# stereo_mixer_quasi_diff_vertical.net
KiCad netlist of a schematic drawn in EAGLE
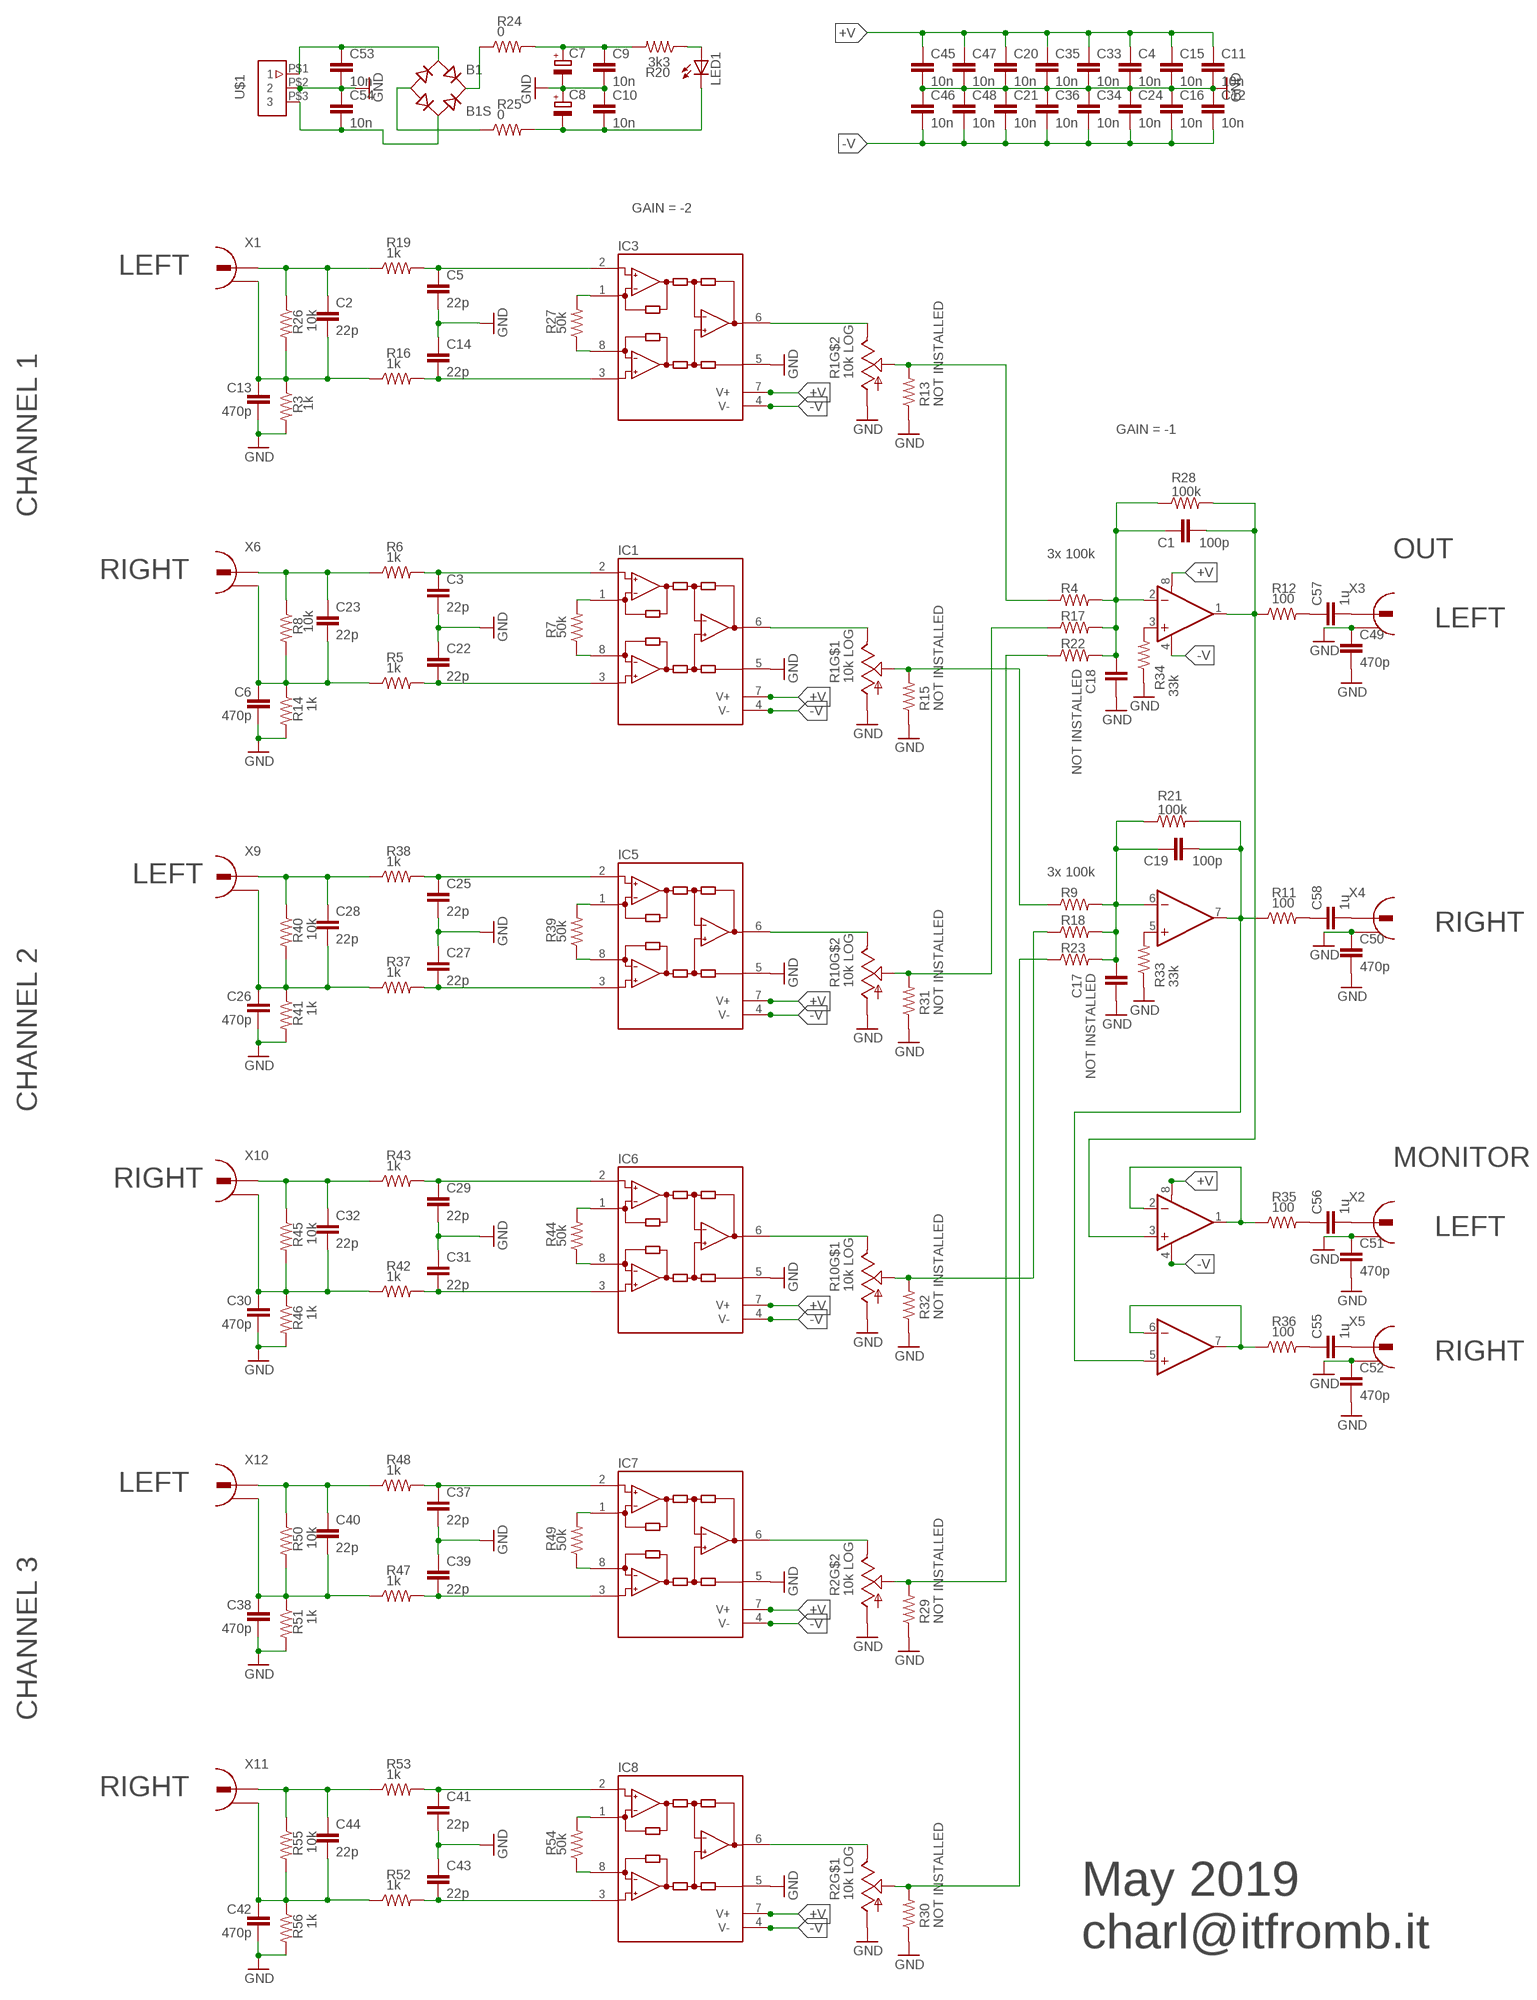
[diagram p0: schematic, sheet 1]

(export (version "E")
  (design (tool "Eeschema 10.0.6"))
  (components
    (comp (ref "B1")
      (value "B1S")
      (footprint "eagle-import:MBS")
      (libsource (lib "eagle-import") (part "BS1"))
    )
    (comp (ref "C1")
      (value "100p")
      (footprint "eagle-import:C1206")
      (libsource (lib "eagle-import") (part "C-EUC1206"))
    )
    (comp (ref "C2")
      (value "22p")
      (footprint "eagle-import:C1206")
      (libsource (lib "eagle-import") (part "C-EUC1206"))
    )
    (comp (ref "C3")
      (value "22p")
      (footprint "eagle-import:C1206")
      (libsource (lib "eagle-import") (part "C-EUC1206"))
    )
    (comp (ref "C4")
      (value "10n")
      (footprint "eagle-import:C1206")
      (libsource (lib "eagle-import") (part "C-EUC1206"))
    )
    (comp (ref "C5")
      (value "22p")
      (footprint "eagle-import:C1206")
      (libsource (lib "eagle-import") (part "C-EUC1206"))
    )
    (comp (ref "C6")
      (value "470p")
      (footprint "eagle-import:C1206")
      (libsource (lib "eagle-import") (part "C-EUC1206"))
    )
    (comp (ref "C7")
      (value "CPOL-EUSANYO_SMD_F12")
      (footprint "eagle-import:SANYO-OSCON_SMD_F12")
      (libsource (lib "eagle-import") (part "CPOL-EUSANYO_SMD_F12"))
    )
    (comp (ref "C8")
      (value "CPOL-EUSANYO_SMD_F12")
      (footprint "eagle-import:SANYO-OSCON_SMD_F12")
      (libsource (lib "eagle-import") (part "CPOL-EUSANYO_SMD_F12"))
    )
    (comp (ref "C9")
      (value "10n")
      (footprint "eagle-import:C1206")
      (libsource (lib "eagle-import") (part "C-EUC1206"))
    )
    (comp (ref "C10")
      (value "10n")
      (footprint "eagle-import:C1206")
      (libsource (lib "eagle-import") (part "C-EUC1206"))
    )
    (comp (ref "C11")
      (value "10n")
      (footprint "eagle-import:C1206")
      (libsource (lib "eagle-import") (part "C-EUC1206"))
    )
    (comp (ref "C12")
      (value "10n")
      (footprint "eagle-import:C1206")
      (libsource (lib "eagle-import") (part "C-EUC1206"))
    )
    (comp (ref "C13")
      (value "470p")
      (footprint "eagle-import:C1206")
      (libsource (lib "eagle-import") (part "C-EUC1206"))
    )
    (comp (ref "C14")
      (value "22p")
      (footprint "eagle-import:C1206")
      (libsource (lib "eagle-import") (part "C-EUC1206"))
    )
    (comp (ref "C15")
      (value "10n")
      (footprint "eagle-import:C1206")
      (libsource (lib "eagle-import") (part "C-EUC1206"))
    )
    (comp (ref "C16")
      (value "10n")
      (footprint "eagle-import:C1206")
      (libsource (lib "eagle-import") (part "C-EUC1206"))
    )
    (comp (ref "C17")
      (value "NOT INSTALLED")
      (footprint "eagle-import:C1206")
      (libsource (lib "eagle-import") (part "C-EUC1206"))
    )
    (comp (ref "C18")
      (value "NOT INSTALLED")
      (footprint "eagle-import:C1206")
      (libsource (lib "eagle-import") (part "C-EUC1206"))
    )
    (comp (ref "C19")
      (value "100p")
      (footprint "eagle-import:C1206")
      (libsource (lib "eagle-import") (part "C-EUC1206"))
    )
    (comp (ref "C20")
      (value "10n")
      (footprint "eagle-import:C1206")
      (libsource (lib "eagle-import") (part "C-EUC1206"))
    )
    (comp (ref "C21")
      (value "10n")
      (footprint "eagle-import:C1206")
      (libsource (lib "eagle-import") (part "C-EUC1206"))
    )
    (comp (ref "C22")
      (value "22p")
      (footprint "eagle-import:C1206")
      (libsource (lib "eagle-import") (part "C-EUC1206"))
    )
    (comp (ref "C23")
      (value "22p")
      (footprint "eagle-import:C1206")
      (libsource (lib "eagle-import") (part "C-EUC1206"))
    )
    (comp (ref "C24")
      (value "10n")
      (footprint "eagle-import:C1206")
      (libsource (lib "eagle-import") (part "C-EUC1206"))
    )
    (comp (ref "C25")
      (value "22p")
      (footprint "eagle-import:C1206")
      (libsource (lib "eagle-import") (part "C-EUC1206"))
    )
    (comp (ref "C26")
      (value "470p")
      (footprint "eagle-import:C1206")
      (libsource (lib "eagle-import") (part "C-EUC1206"))
    )
    (comp (ref "C27")
      (value "22p")
      (footprint "eagle-import:C1206")
      (libsource (lib "eagle-import") (part "C-EUC1206"))
    )
    (comp (ref "C28")
      (value "22p")
      (footprint "eagle-import:C1206")
      (libsource (lib "eagle-import") (part "C-EUC1206"))
    )
    (comp (ref "C29")
      (value "22p")
      (footprint "eagle-import:C1206")
      (libsource (lib "eagle-import") (part "C-EUC1206"))
    )
    (comp (ref "C30")
      (value "470p")
      (footprint "eagle-import:C1206")
      (libsource (lib "eagle-import") (part "C-EUC1206"))
    )
    (comp (ref "C31")
      (value "22p")
      (footprint "eagle-import:C1206")
      (libsource (lib "eagle-import") (part "C-EUC1206"))
    )
    (comp (ref "C32")
      (value "22p")
      (footprint "eagle-import:C1206")
      (libsource (lib "eagle-import") (part "C-EUC1206"))
    )
    (comp (ref "C33")
      (value "10n")
      (footprint "eagle-import:C1206")
      (libsource (lib "eagle-import") (part "C-EUC1206"))
    )
    (comp (ref "C34")
      (value "10n")
      (footprint "eagle-import:C1206")
      (libsource (lib "eagle-import") (part "C-EUC1206"))
    )
    (comp (ref "C35")
      (value "10n")
      (footprint "eagle-import:C1206")
      (libsource (lib "eagle-import") (part "C-EUC1206"))
    )
    (comp (ref "C36")
      (value "10n")
      (footprint "eagle-import:C1206")
      (libsource (lib "eagle-import") (part "C-EUC1206"))
    )
    (comp (ref "C37")
      (value "22p")
      (footprint "eagle-import:C1206")
      (libsource (lib "eagle-import") (part "C-EUC1206"))
    )
    (comp (ref "C38")
      (value "470p")
      (footprint "eagle-import:C1206")
      (libsource (lib "eagle-import") (part "C-EUC1206"))
    )
    (comp (ref "C39")
      (value "22p")
      (footprint "eagle-import:C1206")
      (libsource (lib "eagle-import") (part "C-EUC1206"))
    )
    (comp (ref "C40")
      (value "22p")
      (footprint "eagle-import:C1206")
      (libsource (lib "eagle-import") (part "C-EUC1206"))
    )
    (comp (ref "C41")
      (value "22p")
      (footprint "eagle-import:C1206")
      (libsource (lib "eagle-import") (part "C-EUC1206"))
    )
    (comp (ref "C42")
      (value "470p")
      (footprint "eagle-import:C1206")
      (libsource (lib "eagle-import") (part "C-EUC1206"))
    )
    (comp (ref "C43")
      (value "22p")
      (footprint "eagle-import:C1206")
      (libsource (lib "eagle-import") (part "C-EUC1206"))
    )
    (comp (ref "C44")
      (value "22p")
      (footprint "eagle-import:C1206")
      (libsource (lib "eagle-import") (part "C-EUC1206"))
    )
    (comp (ref "C45")
      (value "10n")
      (footprint "eagle-import:C1206")
      (libsource (lib "eagle-import") (part "C-EUC1206"))
    )
    (comp (ref "C46")
      (value "10n")
      (footprint "eagle-import:C1206")
      (libsource (lib "eagle-import") (part "C-EUC1206"))
    )
    (comp (ref "C47")
      (value "10n")
      (footprint "eagle-import:C1206")
      (libsource (lib "eagle-import") (part "C-EUC1206"))
    )
    (comp (ref "C48")
      (value "10n")
      (footprint "eagle-import:C1206")
      (libsource (lib "eagle-import") (part "C-EUC1206"))
    )
    (comp (ref "C49")
      (value "470p")
      (footprint "eagle-import:C1206")
      (libsource (lib "eagle-import") (part "C-EUC1206"))
    )
    (comp (ref "C50")
      (value "470p")
      (footprint "eagle-import:C1206")
      (libsource (lib "eagle-import") (part "C-EUC1206"))
    )
    (comp (ref "C51")
      (value "470p")
      (footprint "eagle-import:C1206")
      (libsource (lib "eagle-import") (part "C-EUC1206"))
    )
    (comp (ref "C52")
      (value "470p")
      (footprint "eagle-import:C1206")
      (libsource (lib "eagle-import") (part "C-EUC1206"))
    )
    (comp (ref "C53")
      (value "10n")
      (footprint "eagle-import:C1206")
      (libsource (lib "eagle-import") (part "C-EUC1206"))
    )
    (comp (ref "C54")
      (value "10n")
      (footprint "eagle-import:C1206")
      (libsource (lib "eagle-import") (part "C-EUC1206"))
    )
    (comp (ref "C55")
      (value "1u")
      (footprint "eagle-import:C1206")
      (libsource (lib "eagle-import") (part "C-EUC1206"))
    )
    (comp (ref "C56")
      (value "1u")
      (footprint "eagle-import:C1206")
      (libsource (lib "eagle-import") (part "C-EUC1206"))
    )
    (comp (ref "C57")
      (value "1u")
      (footprint "eagle-import:C1206")
      (libsource (lib "eagle-import") (part "C-EUC1206"))
    )
    (comp (ref "C58")
      (value "1u")
      (footprint "eagle-import:C1206")
      (libsource (lib "eagle-import") (part "C-EUC1206"))
    )
    (comp (ref "IC1")
      (value "INA118U")
      (footprint "eagle-import:SO08")
      (fields (field (name "MF") "TEXAS INSTRUMENTS"))
      (libsource (lib "eagle-import") (part "INA118U"))
    )
    (comp (ref "IC2")
      (value "OPAMP-DUALU")
      (footprint "eagle-import:SO08")
      (libsource (lib "eagle-import") (part "OPAMP-DUALU"))
    )
    (comp (ref "IC3")
      (value "INA118U")
      (footprint "eagle-import:SO08")
      (fields (field (name "MF") "TEXAS INSTRUMENTS"))
      (libsource (lib "eagle-import") (part "INA118U"))
    )
    (comp (ref "IC4")
      (value "OPAMP-DUALU")
      (footprint "eagle-import:SO08")
      (libsource (lib "eagle-import") (part "OPAMP-DUALU"))
    )
    (comp (ref "IC5")
      (value "INA118U")
      (footprint "eagle-import:SO08")
      (fields (field (name "MF") "TEXAS INSTRUMENTS"))
      (libsource (lib "eagle-import") (part "INA118U"))
    )
    (comp (ref "IC6")
      (value "INA118U")
      (footprint "eagle-import:SO08")
      (fields (field (name "MF") "TEXAS INSTRUMENTS"))
      (libsource (lib "eagle-import") (part "INA118U"))
    )
    (comp (ref "IC7")
      (value "INA118U")
      (footprint "eagle-import:SO08")
      (fields (field (name "MF") "TEXAS INSTRUMENTS"))
      (libsource (lib "eagle-import") (part "INA118U"))
    )
    (comp (ref "IC8")
      (value "INA118U")
      (footprint "eagle-import:SO08")
      (fields (field (name "MF") "TEXAS INSTRUMENTS"))
      (libsource (lib "eagle-import") (part "INA118U"))
    )
    (comp (ref "LED1")
      (value "LEDCHIPLED_1206")
      (footprint "eagle-import:CHIPLED_1206")
      (libsource (lib "eagle-import") (part "LEDCHIPLED_1206"))
    )
    (comp (ref "R1")
      (value "10k LOG")
      (footprint "eagle-import:SLIDE_POT_REAR_CONN")
      (libsource (lib "eagle-import") (part "TRIM_US-"))
    )
    (comp (ref "R2")
      (value "10k LOG")
      (footprint "eagle-import:SLIDE_POT_REAR_CONN")
      (libsource (lib "eagle-import") (part "TRIM_US-"))
    )
    (comp (ref "R3")
      (value "1k")
      (footprint "eagle-import:M1206")
      (libsource (lib "eagle-import") (part "R-US_M1206"))
    )
    (comp (ref "R4")
      (value "100k")
      (footprint "eagle-import:M1206")
      (libsource (lib "eagle-import") (part "R-US_M1206"))
    )
    (comp (ref "R5")
      (value "1k")
      (footprint "eagle-import:M1206")
      (libsource (lib "eagle-import") (part "R-US_M1206"))
    )
    (comp (ref "R6")
      (value "1k")
      (footprint "eagle-import:M1206")
      (libsource (lib "eagle-import") (part "R-US_M1206"))
    )
    (comp (ref "R7")
      (value "50k")
      (footprint "eagle-import:M1206")
      (libsource (lib "eagle-import") (part "R-US_M1206"))
    )
    (comp (ref "R8")
      (value "10k")
      (footprint "eagle-import:M1206")
      (libsource (lib "eagle-import") (part "R-US_M1206"))
    )
    (comp (ref "R9")
      (value "100k")
      (footprint "eagle-import:M1206")
      (libsource (lib "eagle-import") (part "R-US_M1206"))
    )
    (comp (ref "R10")
      (value "10k LOG")
      (footprint "eagle-import:SLIDE_POT_REAR_CONN")
      (libsource (lib "eagle-import") (part "TRIM_US-"))
    )
    (comp (ref "R11")
      (value "100")
      (footprint "eagle-import:M1206")
      (libsource (lib "eagle-import") (part "R-US_M1206"))
    )
    (comp (ref "R12")
      (value "100")
      (footprint "eagle-import:M1206")
      (libsource (lib "eagle-import") (part "R-US_M1206"))
    )
    (comp (ref "R13")
      (value "NOT INSTALLED")
      (footprint "eagle-import:M1206")
      (libsource (lib "eagle-import") (part "R-US_M1206"))
    )
    (comp (ref "R14")
      (value "1k")
      (footprint "eagle-import:M1206")
      (libsource (lib "eagle-import") (part "R-US_M1206"))
    )
    (comp (ref "R15")
      (value "NOT INSTALLED")
      (footprint "eagle-import:M1206")
      (libsource (lib "eagle-import") (part "R-US_M1206"))
    )
    (comp (ref "R16")
      (value "1k")
      (footprint "eagle-import:M1206")
      (libsource (lib "eagle-import") (part "R-US_M1206"))
    )
    (comp (ref "R17")
      (value "100k")
      (footprint "eagle-import:M1206")
      (libsource (lib "eagle-import") (part "R-US_M1206"))
    )
    (comp (ref "R18")
      (value "100k")
      (footprint "eagle-import:M1206")
      (libsource (lib "eagle-import") (part "R-US_M1206"))
    )
    (comp (ref "R19")
      (value "1k")
      (footprint "eagle-import:M1206")
      (libsource (lib "eagle-import") (part "R-US_M1206"))
    )
    (comp (ref "R20")
      (value "3k3")
      (footprint "eagle-import:M1206")
      (libsource (lib "eagle-import") (part "R-US_M1206"))
    )
    (comp (ref "R21")
      (value "100k")
      (footprint "eagle-import:M1206")
      (libsource (lib "eagle-import") (part "R-US_M1206"))
    )
    (comp (ref "R22")
      (value "100k")
      (footprint "eagle-import:M1206")
      (libsource (lib "eagle-import") (part "R-US_M1206"))
    )
    (comp (ref "R23")
      (value "100k")
      (footprint "eagle-import:M1206")
      (libsource (lib "eagle-import") (part "R-US_M1206"))
    )
    (comp (ref "R24")
      (value "0")
      (footprint "eagle-import:M1206")
      (libsource (lib "eagle-import") (part "R-US_M1206"))
    )
    (comp (ref "R25")
      (value "0")
      (footprint "eagle-import:M1206")
      (libsource (lib "eagle-import") (part "R-US_M1206"))
    )
    (comp (ref "R26")
      (value "10k")
      (footprint "eagle-import:M1206")
      (libsource (lib "eagle-import") (part "R-US_M1206"))
    )
    (comp (ref "R27")
      (value "50k")
      (footprint "eagle-import:M1206")
      (libsource (lib "eagle-import") (part "R-US_M1206"))
    )
    (comp (ref "R28")
      (value "100k")
      (footprint "eagle-import:M1206")
      (libsource (lib "eagle-import") (part "R-US_M1206"))
    )
    (comp (ref "R29")
      (value "NOT INSTALLED")
      (footprint "eagle-import:M1206")
      (libsource (lib "eagle-import") (part "R-US_M1206"))
    )
    (comp (ref "R30")
      (value "NOT INSTALLED")
      (footprint "eagle-import:M1206")
      (libsource (lib "eagle-import") (part "R-US_M1206"))
    )
    (comp (ref "R31")
      (value "NOT INSTALLED")
      (footprint "eagle-import:M1206")
      (libsource (lib "eagle-import") (part "R-US_M1206"))
    )
    (comp (ref "R32")
      (value "NOT INSTALLED")
      (footprint "eagle-import:M1206")
      (libsource (lib "eagle-import") (part "R-US_M1206"))
    )
    (comp (ref "R33")
      (value "33k")
      (footprint "eagle-import:M1206")
      (libsource (lib "eagle-import") (part "R-US_M1206"))
    )
    (comp (ref "R34")
      (value "33k")
      (footprint "eagle-import:M1206")
      (libsource (lib "eagle-import") (part "R-US_M1206"))
    )
    (comp (ref "R35")
      (value "100")
      (footprint "eagle-import:M1206")
      (libsource (lib "eagle-import") (part "R-US_M1206"))
    )
    (comp (ref "R36")
      (value "100")
      (footprint "eagle-import:M1206")
      (libsource (lib "eagle-import") (part "R-US_M1206"))
    )
    (comp (ref "R37")
      (value "1k")
      (footprint "eagle-import:M1206")
      (libsource (lib "eagle-import") (part "R-US_M1206"))
    )
    (comp (ref "R38")
      (value "1k")
      (footprint "eagle-import:M1206")
      (libsource (lib "eagle-import") (part "R-US_M1206"))
    )
    (comp (ref "R39")
      (value "50k")
      (footprint "eagle-import:M1206")
      (libsource (lib "eagle-import") (part "R-US_M1206"))
    )
    (comp (ref "R40")
      (value "10k")
      (footprint "eagle-import:M1206")
      (libsource (lib "eagle-import") (part "R-US_M1206"))
    )
    (comp (ref "R41")
      (value "1k")
      (footprint "eagle-import:M1206")
      (libsource (lib "eagle-import") (part "R-US_M1206"))
    )
    (comp (ref "R42")
      (value "1k")
      (footprint "eagle-import:M1206")
      (libsource (lib "eagle-import") (part "R-US_M1206"))
    )
    (comp (ref "R43")
      (value "1k")
      (footprint "eagle-import:M1206")
      (libsource (lib "eagle-import") (part "R-US_M1206"))
    )
    (comp (ref "R44")
      (value "50k")
      (footprint "eagle-import:M1206")
      (libsource (lib "eagle-import") (part "R-US_M1206"))
    )
    (comp (ref "R45")
      (value "10k")
      (footprint "eagle-import:M1206")
      (libsource (lib "eagle-import") (part "R-US_M1206"))
    )
    (comp (ref "R46")
      (value "1k")
      (footprint "eagle-import:M1206")
      (libsource (lib "eagle-import") (part "R-US_M1206"))
    )
    (comp (ref "R47")
      (value "1k")
      (footprint "eagle-import:M1206")
      (libsource (lib "eagle-import") (part "R-US_M1206"))
    )
    (comp (ref "R48")
      (value "1k")
      (footprint "eagle-import:M1206")
      (libsource (lib "eagle-import") (part "R-US_M1206"))
    )
    (comp (ref "R49")
      (value "50k")
      (footprint "eagle-import:M1206")
      (libsource (lib "eagle-import") (part "R-US_M1206"))
    )
    (comp (ref "R50")
      (value "10k")
      (footprint "eagle-import:M1206")
      (libsource (lib "eagle-import") (part "R-US_M1206"))
    )
    (comp (ref "R51")
      (value "1k")
      (footprint "eagle-import:M1206")
      (libsource (lib "eagle-import") (part "R-US_M1206"))
    )
    (comp (ref "R52")
      (value "1k")
      (footprint "eagle-import:M1206")
      (libsource (lib "eagle-import") (part "R-US_M1206"))
    )
    (comp (ref "R53")
      (value "1k")
      (footprint "eagle-import:M1206")
      (libsource (lib "eagle-import") (part "R-US_M1206"))
    )
    (comp (ref "R54")
      (value "50k")
      (footprint "eagle-import:M1206")
      (libsource (lib "eagle-import") (part "R-US_M1206"))
    )
    (comp (ref "R55")
      (value "10k")
      (footprint "eagle-import:M1206")
      (libsource (lib "eagle-import") (part "R-US_M1206"))
    )
    (comp (ref "R56")
      (value "1k")
      (footprint "eagle-import:M1206")
      (libsource (lib "eagle-import") (part "R-US_M1206"))
    )
    (comp (ref "U$1")
      (value "3-PIN-JST-CONN-1.25MM-PITCH")
      (footprint "eagle-import:S3B-PH-VERTICAL")
      (libsource (lib "eagle-import") (part "3-PIN-JST-CONN-1.25MM-PITCH"))
    )
    (comp (ref "X1")
      (value "736880-49RCA-REAR-MOUNT")
      (footprint "eagle-import:RCA-REAR-MOUNT")
      (libsource (lib "eagle-import") (part "736880-49RCA-REAR-MOUNT"))
    )
    (comp (ref "X2")
      (value "736880-49")
      (footprint "eagle-import:RCA-REAR-MOUNT-CENTER-ONLY")
      (libsource (lib "eagle-import") (part "736880-49"))
    )
    (comp (ref "X3")
      (value "736880-49")
      (footprint "eagle-import:RCA-REAR-MOUNT-CENTER-ONLY")
      (libsource (lib "eagle-import") (part "736880-49"))
    )
    (comp (ref "X4")
      (value "736880-49")
      (footprint "eagle-import:RCA-REAR-MOUNT-CENTER-ONLY")
      (libsource (lib "eagle-import") (part "736880-49"))
    )
    (comp (ref "X5")
      (value "736880-49")
      (footprint "eagle-import:RCA-REAR-MOUNT-CENTER-ONLY")
      (libsource (lib "eagle-import") (part "736880-49"))
    )
    (comp (ref "X6")
      (value "736880-49RCA-REAR-MOUNT")
      (footprint "eagle-import:RCA-REAR-MOUNT")
      (libsource (lib "eagle-import") (part "736880-49RCA-REAR-MOUNT"))
    )
    (comp (ref "X9")
      (value "736880-49RCA-REAR-MOUNT")
      (footprint "eagle-import:RCA-REAR-MOUNT")
      (libsource (lib "eagle-import") (part "736880-49RCA-REAR-MOUNT"))
    )
    (comp (ref "X10")
      (value "736880-49RCA-REAR-MOUNT")
      (footprint "eagle-import:RCA-REAR-MOUNT")
      (libsource (lib "eagle-import") (part "736880-49RCA-REAR-MOUNT"))
    )
    (comp (ref "X11")
      (value "736880-49RCA-REAR-MOUNT")
      (footprint "eagle-import:RCA-REAR-MOUNT")
      (libsource (lib "eagle-import") (part "736880-49RCA-REAR-MOUNT"))
    )
    (comp (ref "X12")
      (value "736880-49RCA-REAR-MOUNT")
      (footprint "eagle-import:RCA-REAR-MOUNT")
      (libsource (lib "eagle-import") (part "736880-49RCA-REAR-MOUNT"))
    )
  )
  (nets
    (net (code "1") (name "+V") (class "Default")
      (node (ref "C11") (pin "1") (pinfunction "1_1") (pintype "passive"))
      (node (ref "C15") (pin "1") (pinfunction "1_1") (pintype "passive"))
      (node (ref "C20") (pin "1") (pinfunction "1_1") (pintype "passive"))
      (node (ref "C33") (pin "1") (pinfunction "1_1") (pintype "passive"))
      (node (ref "C35") (pin "1") (pinfunction "1_1") (pintype "passive"))
      (node (ref "C4") (pin "1") (pinfunction "1_1") (pintype "passive"))
      (node (ref "C45") (pin "1") (pinfunction "1_1") (pintype "passive"))
      (node (ref "C47") (pin "1") (pinfunction "1_1") (pintype "passive"))
      (node (ref "C7") (pin "+") (pinfunction "+_+") (pintype "passive"))
      (node (ref "C9") (pin "1") (pinfunction "1_1") (pintype "passive"))
      (node (ref "IC1") (pin "7") (pinfunction "V+_7") (pintype "power_in"))
      (node (ref "IC2") (pin "8") (pinfunction "V+_8") (pintype "power_in"))
      (node (ref "IC3") (pin "7") (pinfunction "V+_7") (pintype "power_in"))
      (node (ref "IC4") (pin "8") (pinfunction "V+_8") (pintype "power_in"))
      (node (ref "IC5") (pin "7") (pinfunction "V+_7") (pintype "power_in"))
      (node (ref "IC6") (pin "7") (pinfunction "V+_7") (pintype "power_in"))
      (node (ref "IC7") (pin "7") (pinfunction "V+_7") (pintype "power_in"))
      (node (ref "IC8") (pin "7") (pinfunction "V+_7") (pintype "power_in"))
      (node (ref "R20") (pin "2") (pinfunction "2_2") (pintype "passive"))
      (node (ref "R24") (pin "2") (pinfunction "2_2") (pintype "passive"))
    )
    (net (code "2") (name "-V") (class "Default")
      (node (ref "C10") (pin "2") (pinfunction "2_2") (pintype "passive"))
      (node (ref "C12") (pin "2") (pinfunction "2_2") (pintype "passive"))
      (node (ref "C16") (pin "2") (pinfunction "2_2") (pintype "passive"))
      (node (ref "C21") (pin "2") (pinfunction "2_2") (pintype "passive"))
      (node (ref "C24") (pin "2") (pinfunction "2_2") (pintype "passive"))
      (node (ref "C34") (pin "2") (pinfunction "2_2") (pintype "passive"))
      (node (ref "C36") (pin "2") (pinfunction "2_2") (pintype "passive"))
      (node (ref "C46") (pin "2") (pinfunction "2_2") (pintype "passive"))
      (node (ref "C48") (pin "2") (pinfunction "2_2") (pintype "passive"))
      (node (ref "C8") (pin "-") (pinfunction "-_-") (pintype "passive"))
      (node (ref "IC1") (pin "4") (pinfunction "V-_4") (pintype "power_in"))
      (node (ref "IC2") (pin "4") (pinfunction "V-_4") (pintype "power_in"))
      (node (ref "IC3") (pin "4") (pinfunction "V-_4") (pintype "power_in"))
      (node (ref "IC4") (pin "4") (pinfunction "V-_4") (pintype "power_in"))
      (node (ref "IC5") (pin "4") (pinfunction "V-_4") (pintype "power_in"))
      (node (ref "IC6") (pin "4") (pinfunction "V-_4") (pintype "power_in"))
      (node (ref "IC7") (pin "4") (pinfunction "V-_4") (pintype "power_in"))
      (node (ref "IC8") (pin "4") (pinfunction "V-_4") (pintype "power_in"))
      (node (ref "LED1") (pin "C") (pinfunction "C_C") (pintype "passive"))
      (node (ref "R25") (pin "2") (pinfunction "2_2") (pintype "passive"))
    )
    (net (code "3") (name "GND") (class "Default")
      (node (ref "C10") (pin "1") (pinfunction "1_1") (pintype "passive"))
      (node (ref "C11") (pin "2") (pinfunction "2_2") (pintype "passive"))
      (node (ref "C12") (pin "1") (pinfunction "1_1") (pintype "passive"))
      (node (ref "C13") (pin "2") (pinfunction "2_2") (pintype "passive"))
      (node (ref "C14") (pin "1") (pinfunction "1_1") (pintype "passive"))
      (node (ref "C15") (pin "2") (pinfunction "2_2") (pintype "passive"))
      (node (ref "C16") (pin "1") (pinfunction "1_1") (pintype "passive"))
      (node (ref "C17") (pin "1") (pinfunction "1_1") (pintype "passive"))
      (node (ref "C18") (pin "1") (pinfunction "1_1") (pintype "passive"))
      (node (ref "C20") (pin "2") (pinfunction "2_2") (pintype "passive"))
      (node (ref "C21") (pin "1") (pinfunction "1_1") (pintype "passive"))
      (node (ref "C22") (pin "1") (pinfunction "1_1") (pintype "passive"))
      (node (ref "C24") (pin "1") (pinfunction "1_1") (pintype "passive"))
      (node (ref "C25") (pin "2") (pinfunction "2_2") (pintype "passive"))
      (node (ref "C26") (pin "2") (pinfunction "2_2") (pintype "passive"))
      (node (ref "C27") (pin "1") (pinfunction "1_1") (pintype "passive"))
      (node (ref "C29") (pin "2") (pinfunction "2_2") (pintype "passive"))
      (node (ref "C3") (pin "2") (pinfunction "2_2") (pintype "passive"))
      (node (ref "C30") (pin "2") (pinfunction "2_2") (pintype "passive"))
      (node (ref "C31") (pin "1") (pinfunction "1_1") (pintype "passive"))
      (node (ref "C33") (pin "2") (pinfunction "2_2") (pintype "passive"))
      (node (ref "C34") (pin "1") (pinfunction "1_1") (pintype "passive"))
      (node (ref "C35") (pin "2") (pinfunction "2_2") (pintype "passive"))
      (node (ref "C36") (pin "1") (pinfunction "1_1") (pintype "passive"))
      (node (ref "C37") (pin "2") (pinfunction "2_2") (pintype "passive"))
      (node (ref "C38") (pin "2") (pinfunction "2_2") (pintype "passive"))
      (node (ref "C39") (pin "1") (pinfunction "1_1") (pintype "passive"))
      (node (ref "C4") (pin "2") (pinfunction "2_2") (pintype "passive"))
      (node (ref "C41") (pin "2") (pinfunction "2_2") (pintype "passive"))
      (node (ref "C42") (pin "2") (pinfunction "2_2") (pintype "passive"))
      (node (ref "C43") (pin "1") (pinfunction "1_1") (pintype "passive"))
      (node (ref "C45") (pin "2") (pinfunction "2_2") (pintype "passive"))
      (node (ref "C46") (pin "1") (pinfunction "1_1") (pintype "passive"))
      (node (ref "C47") (pin "2") (pinfunction "2_2") (pintype "passive"))
      (node (ref "C48") (pin "1") (pinfunction "1_1") (pintype "passive"))
      (node (ref "C49") (pin "1") (pinfunction "1_1") (pintype "passive"))
      (node (ref "C49") (pin "2") (pinfunction "2_2") (pintype "passive"))
      (node (ref "C5") (pin "2") (pinfunction "2_2") (pintype "passive"))
      (node (ref "C50") (pin "1") (pinfunction "1_1") (pintype "passive"))
      (node (ref "C50") (pin "2") (pinfunction "2_2") (pintype "passive"))
      (node (ref "C51") (pin "1") (pinfunction "1_1") (pintype "passive"))
      (node (ref "C51") (pin "2") (pinfunction "2_2") (pintype "passive"))
      (node (ref "C52") (pin "1") (pinfunction "1_1") (pintype "passive"))
      (node (ref "C52") (pin "2") (pinfunction "2_2") (pintype "passive"))
      (node (ref "C53") (pin "2") (pinfunction "2_2") (pintype "passive"))
      (node (ref "C54") (pin "1") (pinfunction "1_1") (pintype "passive"))
      (node (ref "C6") (pin "2") (pinfunction "2_2") (pintype "passive"))
      (node (ref "C7") (pin "-") (pinfunction "-_-") (pintype "passive"))
      (node (ref "C8") (pin "+") (pinfunction "+_+") (pintype "passive"))
      (node (ref "C9") (pin "2") (pinfunction "2_2") (pintype "passive"))
      (node (ref "IC1") (pin "5") (pinfunction "REF_5") (pintype "passive"))
      (node (ref "IC3") (pin "5") (pinfunction "REF_5") (pintype "passive"))
      (node (ref "IC5") (pin "5") (pinfunction "REF_5") (pintype "passive"))
      (node (ref "IC6") (pin "5") (pinfunction "REF_5") (pintype "passive"))
      (node (ref "IC7") (pin "5") (pinfunction "REF_5") (pintype "passive"))
      (node (ref "IC8") (pin "5") (pinfunction "REF_5") (pintype "passive"))
      (node (ref "R1") (pin "R1A") (pinfunction "RA_R1A") (pintype "passive"))
      (node (ref "R1") (pin "R2A") (pinfunction "RA_R2A") (pintype "passive"))
      (node (ref "R10") (pin "R1A") (pinfunction "RA_R1A") (pintype "passive"))
      (node (ref "R10") (pin "R2A") (pinfunction "RA_R2A") (pintype "passive"))
      (node (ref "R13") (pin "1") (pinfunction "1_1") (pintype "passive"))
      (node (ref "R14") (pin "2") (pinfunction "2_2") (pintype "passive"))
      (node (ref "R15") (pin "1") (pinfunction "1_1") (pintype "passive"))
      (node (ref "R2") (pin "R1A") (pinfunction "RA_R1A") (pintype "passive"))
      (node (ref "R2") (pin "R2A") (pinfunction "RA_R2A") (pintype "passive"))
      (node (ref "R29") (pin "1") (pinfunction "1_1") (pintype "passive"))
      (node (ref "R3") (pin "2") (pinfunction "2_2") (pintype "passive"))
      (node (ref "R30") (pin "1") (pinfunction "1_1") (pintype "passive"))
      (node (ref "R31") (pin "1") (pinfunction "1_1") (pintype "passive"))
      (node (ref "R32") (pin "1") (pinfunction "1_1") (pintype "passive"))
      (node (ref "R33") (pin "1") (pinfunction "1_1") (pintype "passive"))
      (node (ref "R34") (pin "1") (pinfunction "1_1") (pintype "passive"))
      (node (ref "R41") (pin "2") (pinfunction "2_2") (pintype "passive"))
      (node (ref "R46") (pin "2") (pinfunction "2_2") (pintype "passive"))
      (node (ref "R51") (pin "2") (pinfunction "2_2") (pintype "passive"))
      (node (ref "R56") (pin "2") (pinfunction "2_2") (pintype "passive"))
      (node (ref "U$1") (pin "P$2") (pinfunction "2_P$2") (pintype "passive"))
      (node (ref "X2") (pin "SIGNAL") (pinfunction "2_SIGNAL") (pintype "passive"))
      (node (ref "X3") (pin "SIGNAL") (pinfunction "2_SIGNAL") (pintype "passive"))
      (node (ref "X4") (pin "SIGNAL") (pinfunction "2_SIGNAL") (pintype "passive"))
      (node (ref "X5") (pin "SIGNAL") (pinfunction "2_SIGNAL") (pintype "passive"))
    )
    (net (code "4") (name "Net-(B1-Pad+)") (class "Default")
      (node (ref "B1") (pin "+") (pinfunction "+_+") (pintype "passive"))
      (node (ref "R24") (pin "1") (pinfunction "1_1") (pintype "passive"))
    )
    (net (code "5") (name "Net-(B1-Pad-)") (class "Default")
      (node (ref "B1") (pin "-") (pinfunction "-_-") (pintype "passive"))
      (node (ref "R25") (pin "1") (pinfunction "1_1") (pintype "passive"))
    )
    (net (code "6") (name "Net-(C55-Pad1)") (class "Default")
      (node (ref "C55") (pin "1") (pinfunction "1_1") (pintype "passive"))
      (node (ref "R36") (pin "2") (pinfunction "2_2") (pintype "passive"))
    )
    (net (code "7") (name "Net-(C56-Pad1)") (class "Default")
      (node (ref "C56") (pin "1") (pinfunction "1_1") (pintype "passive"))
      (node (ref "R35") (pin "2") (pinfunction "2_2") (pintype "passive"))
    )
    (net (code "8") (name "Net-(C57-Pad1)") (class "Default")
      (node (ref "C57") (pin "1") (pinfunction "1_1") (pintype "passive"))
      (node (ref "R12") (pin "2") (pinfunction "2_2") (pintype "passive"))
    )
    (net (code "9") (name "Net-(C58-Pad1)") (class "Default")
      (node (ref "C58") (pin "1") (pinfunction "1_1") (pintype "passive"))
      (node (ref "R11") (pin "2") (pinfunction "2_2") (pintype "passive"))
    )
    (net (code "10") (name "Net-(IC1-+IN)") (class "Default")
      (node (ref "C22") (pin "2") (pinfunction "2_2") (pintype "passive"))
      (node (ref "IC1") (pin "3") (pinfunction "+IN_3") (pintype "input"))
      (node (ref "R5") (pin "2") (pinfunction "2_2") (pintype "passive"))
    )
    (net (code "11") (name "Net-(IC1--IN)") (class "Default")
      (node (ref "C3") (pin "1") (pinfunction "1_1") (pintype "passive"))
      (node (ref "IC1") (pin "2") (pinfunction "-IN_2") (pintype "input"))
      (node (ref "R6") (pin "2") (pinfunction "2_2") (pintype "passive"))
    )
    (net (code "12") (name "Net-(IC1-OUT)") (class "Default")
      (node (ref "IC1") (pin "6") (pinfunction "OUT_6") (pintype "output"))
      (node (ref "R1") (pin "R1B") (pinfunction "RB_R1B") (pintype "passive"))
    )
    (net (code "13") (name "Net-(IC1-RG-Pad1)") (class "Default")
      (node (ref "IC1") (pin "1") (pinfunction "RG_1") (pintype "passive"))
      (node (ref "R7") (pin "2") (pinfunction "2_2") (pintype "passive"))
    )
    (net (code "14") (name "Net-(IC1-RG-Pad8)") (class "Default")
      (node (ref "IC1") (pin "8") (pinfunction "RG_8") (pintype "passive"))
      (node (ref "R7") (pin "1") (pinfunction "1_1") (pintype "passive"))
    )
    (net (code "15") (name "Net-(IC2A-+IN)") (class "Default")
      (node (ref "IC2") (pin "3") (pinfunction "+IN_3") (pintype "input"))
      (node (ref "R34") (pin "2") (pinfunction "2_2") (pintype "passive"))
    )
    (net (code "16") (name "Net-(IC2A--IN)") (class "Default")
      (node (ref "C1") (pin "1") (pinfunction "1_1") (pintype "passive"))
      (node (ref "C18") (pin "2") (pinfunction "2_2") (pintype "passive"))
      (node (ref "IC2") (pin "2") (pinfunction "-IN_2") (pintype "input"))
      (node (ref "R17") (pin "2") (pinfunction "2_2") (pintype "passive"))
      (node (ref "R22") (pin "2") (pinfunction "2_2") (pintype "passive"))
      (node (ref "R28") (pin "1") (pinfunction "1_1") (pintype "passive"))
      (node (ref "R4") (pin "2") (pinfunction "2_2") (pintype "passive"))
    )
    (net (code "17") (name "Net-(IC2A-OUT)") (class "Default")
      (node (ref "C1") (pin "2") (pinfunction "2_2") (pintype "passive"))
      (node (ref "IC2") (pin "1") (pinfunction "OUT_1") (pintype "output"))
      (node (ref "IC4") (pin "3") (pinfunction "+IN_3") (pintype "input"))
      (node (ref "R12") (pin "1") (pinfunction "1_1") (pintype "passive"))
      (node (ref "R28") (pin "2") (pinfunction "2_2") (pintype "passive"))
    )
    (net (code "18") (name "Net-(IC2B-+IN)") (class "Default")
      (node (ref "IC2") (pin "5") (pinfunction "+IN_5") (pintype "input"))
      (node (ref "R33") (pin "2") (pinfunction "2_2") (pintype "passive"))
    )
    (net (code "19") (name "Net-(IC2B--IN)") (class "Default")
      (node (ref "C17") (pin "2") (pinfunction "2_2") (pintype "passive"))
      (node (ref "C19") (pin "1") (pinfunction "1_1") (pintype "passive"))
      (node (ref "IC2") (pin "6") (pinfunction "-IN_6") (pintype "input"))
      (node (ref "R18") (pin "2") (pinfunction "2_2") (pintype "passive"))
      (node (ref "R21") (pin "1") (pinfunction "1_1") (pintype "passive"))
      (node (ref "R23") (pin "2") (pinfunction "2_2") (pintype "passive"))
      (node (ref "R9") (pin "2") (pinfunction "2_2") (pintype "passive"))
    )
    (net (code "20") (name "Net-(IC2B-OUT)") (class "Default")
      (node (ref "C19") (pin "2") (pinfunction "2_2") (pintype "passive"))
      (node (ref "IC2") (pin "7") (pinfunction "OUT_7") (pintype "output"))
      (node (ref "IC4") (pin "5") (pinfunction "+IN_5") (pintype "input"))
      (node (ref "R11") (pin "1") (pinfunction "1_1") (pintype "passive"))
      (node (ref "R21") (pin "2") (pinfunction "2_2") (pintype "passive"))
    )
    (net (code "21") (name "Net-(IC3-+IN)") (class "Default")
      (node (ref "C14") (pin "2") (pinfunction "2_2") (pintype "passive"))
      (node (ref "IC3") (pin "3") (pinfunction "+IN_3") (pintype "input"))
      (node (ref "R16") (pin "2") (pinfunction "2_2") (pintype "passive"))
    )
    (net (code "22") (name "Net-(IC3--IN)") (class "Default")
      (node (ref "C5") (pin "1") (pinfunction "1_1") (pintype "passive"))
      (node (ref "IC3") (pin "2") (pinfunction "-IN_2") (pintype "input"))
      (node (ref "R19") (pin "2") (pinfunction "2_2") (pintype "passive"))
    )
    (net (code "23") (name "Net-(IC3-OUT)") (class "Default")
      (node (ref "IC3") (pin "6") (pinfunction "OUT_6") (pintype "output"))
      (node (ref "R1") (pin "R2B") (pinfunction "RB_R2B") (pintype "passive"))
    )
    (net (code "24") (name "Net-(IC3-RG-Pad1)") (class "Default")
      (node (ref "IC3") (pin "1") (pinfunction "RG_1") (pintype "passive"))
      (node (ref "R27") (pin "2") (pinfunction "2_2") (pintype "passive"))
    )
    (net (code "25") (name "Net-(IC3-RG-Pad8)") (class "Default")
      (node (ref "IC3") (pin "8") (pinfunction "RG_8") (pintype "passive"))
      (node (ref "R27") (pin "1") (pinfunction "1_1") (pintype "passive"))
    )
    (net (code "26") (name "Net-(IC4A--IN)") (class "Default")
      (node (ref "IC4") (pin "1") (pinfunction "OUT_1") (pintype "output"))
      (node (ref "IC4") (pin "2") (pinfunction "-IN_2") (pintype "input"))
      (node (ref "R35") (pin "1") (pinfunction "1_1") (pintype "passive"))
    )
    (net (code "27") (name "Net-(IC4B--IN)") (class "Default")
      (node (ref "IC4") (pin "6") (pinfunction "-IN_6") (pintype "input"))
      (node (ref "IC4") (pin "7") (pinfunction "OUT_7") (pintype "output"))
      (node (ref "R36") (pin "1") (pinfunction "1_1") (pintype "passive"))
    )
    (net (code "28") (name "Net-(IC5-+IN)") (class "Default")
      (node (ref "C27") (pin "2") (pinfunction "2_2") (pintype "passive"))
      (node (ref "IC5") (pin "3") (pinfunction "+IN_3") (pintype "input"))
      (node (ref "R37") (pin "2") (pinfunction "2_2") (pintype "passive"))
    )
    (net (code "29") (name "Net-(IC5--IN)") (class "Default")
      (node (ref "C25") (pin "1") (pinfunction "1_1") (pintype "passive"))
      (node (ref "IC5") (pin "2") (pinfunction "-IN_2") (pintype "input"))
      (node (ref "R38") (pin "2") (pinfunction "2_2") (pintype "passive"))
    )
    (net (code "30") (name "Net-(IC5-OUT)") (class "Default")
      (node (ref "IC5") (pin "6") (pinfunction "OUT_6") (pintype "output"))
      (node (ref "R10") (pin "R2B") (pinfunction "RB_R2B") (pintype "passive"))
    )
    (net (code "31") (name "Net-(IC5-RG-Pad1)") (class "Default")
      (node (ref "IC5") (pin "1") (pinfunction "RG_1") (pintype "passive"))
      (node (ref "R39") (pin "2") (pinfunction "2_2") (pintype "passive"))
    )
    (net (code "32") (name "Net-(IC5-RG-Pad8)") (class "Default")
      (node (ref "IC5") (pin "8") (pinfunction "RG_8") (pintype "passive"))
      (node (ref "R39") (pin "1") (pinfunction "1_1") (pintype "passive"))
    )
    (net (code "33") (name "Net-(IC6-+IN)") (class "Default")
      (node (ref "C31") (pin "2") (pinfunction "2_2") (pintype "passive"))
      (node (ref "IC6") (pin "3") (pinfunction "+IN_3") (pintype "input"))
      (node (ref "R42") (pin "2") (pinfunction "2_2") (pintype "passive"))
    )
    (net (code "34") (name "Net-(IC6--IN)") (class "Default")
      (node (ref "C29") (pin "1") (pinfunction "1_1") (pintype "passive"))
      (node (ref "IC6") (pin "2") (pinfunction "-IN_2") (pintype "input"))
      (node (ref "R43") (pin "2") (pinfunction "2_2") (pintype "passive"))
    )
    (net (code "35") (name "Net-(IC6-OUT)") (class "Default")
      (node (ref "IC6") (pin "6") (pinfunction "OUT_6") (pintype "output"))
      (node (ref "R10") (pin "R1B") (pinfunction "RB_R1B") (pintype "passive"))
    )
    (net (code "36") (name "Net-(IC6-RG-Pad1)") (class "Default")
      (node (ref "IC6") (pin "1") (pinfunction "RG_1") (pintype "passive"))
      (node (ref "R44") (pin "2") (pinfunction "2_2") (pintype "passive"))
    )
    (net (code "37") (name "Net-(IC6-RG-Pad8)") (class "Default")
      (node (ref "IC6") (pin "8") (pinfunction "RG_8") (pintype "passive"))
      (node (ref "R44") (pin "1") (pinfunction "1_1") (pintype "passive"))
    )
    (net (code "38") (name "Net-(IC7-+IN)") (class "Default")
      (node (ref "C39") (pin "2") (pinfunction "2_2") (pintype "passive"))
      (node (ref "IC7") (pin "3") (pinfunction "+IN_3") (pintype "input"))
      (node (ref "R47") (pin "2") (pinfunction "2_2") (pintype "passive"))
    )
    (net (code "39") (name "Net-(IC7--IN)") (class "Default")
      (node (ref "C37") (pin "1") (pinfunction "1_1") (pintype "passive"))
      (node (ref "IC7") (pin "2") (pinfunction "-IN_2") (pintype "input"))
      (node (ref "R48") (pin "2") (pinfunction "2_2") (pintype "passive"))
    )
    (net (code "40") (name "Net-(IC7-OUT)") (class "Default")
      (node (ref "IC7") (pin "6") (pinfunction "OUT_6") (pintype "output"))
      (node (ref "R2") (pin "R2B") (pinfunction "RB_R2B") (pintype "passive"))
    )
    (net (code "41") (name "Net-(IC7-RG-Pad1)") (class "Default")
      (node (ref "IC7") (pin "1") (pinfunction "RG_1") (pintype "passive"))
      (node (ref "R49") (pin "2") (pinfunction "2_2") (pintype "passive"))
    )
    (net (code "42") (name "Net-(IC7-RG-Pad8)") (class "Default")
      (node (ref "IC7") (pin "8") (pinfunction "RG_8") (pintype "passive"))
      (node (ref "R49") (pin "1") (pinfunction "1_1") (pintype "passive"))
    )
    (net (code "43") (name "Net-(IC8-+IN)") (class "Default")
      (node (ref "C43") (pin "2") (pinfunction "2_2") (pintype "passive"))
      (node (ref "IC8") (pin "3") (pinfunction "+IN_3") (pintype "input"))
      (node (ref "R52") (pin "2") (pinfunction "2_2") (pintype "passive"))
    )
    (net (code "44") (name "Net-(IC8--IN)") (class "Default")
      (node (ref "C41") (pin "1") (pinfunction "1_1") (pintype "passive"))
      (node (ref "IC8") (pin "2") (pinfunction "-IN_2") (pintype "input"))
      (node (ref "R53") (pin "2") (pinfunction "2_2") (pintype "passive"))
    )
    (net (code "45") (name "Net-(IC8-OUT)") (class "Default")
      (node (ref "IC8") (pin "6") (pinfunction "OUT_6") (pintype "output"))
      (node (ref "R2") (pin "R1B") (pinfunction "RB_R1B") (pintype "passive"))
    )
    (net (code "46") (name "Net-(IC8-RG-Pad1)") (class "Default")
      (node (ref "IC8") (pin "1") (pinfunction "RG_1") (pintype "passive"))
      (node (ref "R54") (pin "2") (pinfunction "2_2") (pintype "passive"))
    )
    (net (code "47") (name "Net-(IC8-RG-Pad8)") (class "Default")
      (node (ref "IC8") (pin "8") (pinfunction "RG_8") (pintype "passive"))
      (node (ref "R54") (pin "1") (pinfunction "1_1") (pintype "passive"))
    )
    (net (code "48") (name "Net-(LED1-PadA)") (class "Default")
      (node (ref "LED1") (pin "A") (pinfunction "A_A") (pintype "passive"))
      (node (ref "R20") (pin "1") (pinfunction "1_1") (pintype "passive"))
    )
    (net (code "49") (name "Net-(R1A-RW)") (class "Default")
      (node (ref "R1") (pin "R1W") (pinfunction "RW_R1W") (pintype "passive"))
      (node (ref "R15") (pin "2") (pinfunction "2_2") (pintype "passive"))
      (node (ref "R9") (pin "1") (pinfunction "1_1") (pintype "passive"))
    )
    (net (code "50") (name "Net-(R1B-RW)") (class "Default")
      (node (ref "R1") (pin "R2W") (pinfunction "RW_R2W") (pintype "passive"))
      (node (ref "R13") (pin "2") (pinfunction "2_2") (pintype "passive"))
      (node (ref "R4") (pin "1") (pinfunction "1_1") (pintype "passive"))
    )
    (net (code "51") (name "Net-(R2A-RW)") (class "Default")
      (node (ref "R2") (pin "R1W") (pinfunction "RW_R1W") (pintype "passive"))
      (node (ref "R23") (pin "1") (pinfunction "1_1") (pintype "passive"))
      (node (ref "R30") (pin "2") (pinfunction "2_2") (pintype "passive"))
    )
    (net (code "52") (name "Net-(R2B-RW)") (class "Default")
      (node (ref "R2") (pin "R2W") (pinfunction "RW_R2W") (pintype "passive"))
      (node (ref "R22") (pin "1") (pinfunction "1_1") (pintype "passive"))
      (node (ref "R29") (pin "2") (pinfunction "2_2") (pintype "passive"))
    )
    (net (code "53") (name "Net-(R10A-RW)") (class "Default")
      (node (ref "R10") (pin "R1W") (pinfunction "RW_R1W") (pintype "passive"))
      (node (ref "R18") (pin "1") (pinfunction "1_1") (pintype "passive"))
      (node (ref "R32") (pin "2") (pinfunction "2_2") (pintype "passive"))
    )
    (net (code "54") (name "Net-(R10B-RW)") (class "Default")
      (node (ref "R10") (pin "R2W") (pinfunction "RW_R2W") (pintype "passive"))
      (node (ref "R17") (pin "1") (pinfunction "1_1") (pintype "passive"))
      (node (ref "R31") (pin "2") (pinfunction "2_2") (pintype "passive"))
    )
    (net (code "55") (name "Net-(U$1-1)") (class "Default")
      (node (ref "B1") (pin "AC1") (pinfunction "AC1_AC1") (pintype "passive"))
      (node (ref "C53") (pin "1") (pinfunction "1_1") (pintype "passive"))
      (node (ref "U$1") (pin "P$1") (pinfunction "1_P$1") (pintype "passive"))
    )
    (net (code "56") (name "Net-(U$1-3)") (class "Default")
      (node (ref "B1") (pin "AC2") (pinfunction "AC2_AC2") (pintype "passive"))
      (node (ref "C54") (pin "2") (pinfunction "2_2") (pintype "passive"))
      (node (ref "U$1") (pin "P$3") (pinfunction "3_P$3") (pintype "passive"))
    )
    (net (code "57") (name "Net-(X1-1)") (class "Default")
      (node (ref "C2") (pin "1") (pinfunction "1_1") (pintype "passive"))
      (node (ref "R19") (pin "1") (pinfunction "1_1") (pintype "passive"))
      (node (ref "R26") (pin "1") (pinfunction "1_1") (pintype "passive"))
      (node (ref "X1") (pin "SIGNAL") (pinfunction "1_SIGNAL") (pintype "passive"))
    )
    (net (code "58") (name "Net-(X1-2)") (class "Default")
      (node (ref "C13") (pin "1") (pinfunction "1_1") (pintype "passive"))
      (node (ref "C2") (pin "2") (pinfunction "2_2") (pintype "passive"))
      (node (ref "R16") (pin "1") (pinfunction "1_1") (pintype "passive"))
      (node (ref "R26") (pin "2") (pinfunction "2_2") (pintype "passive"))
      (node (ref "R3") (pin "1") (pinfunction "1_1") (pintype "passive"))
      (node (ref "X1") (pin "RING") (pinfunction "2_RING") (pintype "passive"))
    )
    (net (code "59") (name "Net-(X2-1)") (class "Default")
      (node (ref "C56") (pin "2") (pinfunction "2_2") (pintype "passive"))
      (node (ref "X2") (pin "RING") (pinfunction "1_RING") (pintype "passive"))
    )
    (net (code "60") (name "Net-(X3-1)") (class "Default")
      (node (ref "C57") (pin "2") (pinfunction "2_2") (pintype "passive"))
      (node (ref "X3") (pin "RING") (pinfunction "1_RING") (pintype "passive"))
    )
    (net (code "61") (name "Net-(X4-1)") (class "Default")
      (node (ref "C58") (pin "2") (pinfunction "2_2") (pintype "passive"))
      (node (ref "X4") (pin "RING") (pinfunction "1_RING") (pintype "passive"))
    )
    (net (code "62") (name "Net-(X5-1)") (class "Default")
      (node (ref "C55") (pin "2") (pinfunction "2_2") (pintype "passive"))
      (node (ref "X5") (pin "RING") (pinfunction "1_RING") (pintype "passive"))
    )
    (net (code "63") (name "Net-(X6-1)") (class "Default")
      (node (ref "C23") (pin "1") (pinfunction "1_1") (pintype "passive"))
      (node (ref "R6") (pin "1") (pinfunction "1_1") (pintype "passive"))
      (node (ref "R8") (pin "1") (pinfunction "1_1") (pintype "passive"))
      (node (ref "X6") (pin "SIGNAL") (pinfunction "1_SIGNAL") (pintype "passive"))
    )
    (net (code "64") (name "Net-(X6-2)") (class "Default")
      (node (ref "C23") (pin "2") (pinfunction "2_2") (pintype "passive"))
      (node (ref "C6") (pin "1") (pinfunction "1_1") (pintype "passive"))
      (node (ref "R14") (pin "1") (pinfunction "1_1") (pintype "passive"))
      (node (ref "R5") (pin "1") (pinfunction "1_1") (pintype "passive"))
      (node (ref "R8") (pin "2") (pinfunction "2_2") (pintype "passive"))
      (node (ref "X6") (pin "RING") (pinfunction "2_RING") (pintype "passive"))
    )
    (net (code "65") (name "Net-(X9-1)") (class "Default")
      (node (ref "C28") (pin "1") (pinfunction "1_1") (pintype "passive"))
      (node (ref "R38") (pin "1") (pinfunction "1_1") (pintype "passive"))
      (node (ref "R40") (pin "1") (pinfunction "1_1") (pintype "passive"))
      (node (ref "X9") (pin "SIGNAL") (pinfunction "1_SIGNAL") (pintype "passive"))
    )
    (net (code "66") (name "Net-(X9-2)") (class "Default")
      (node (ref "C26") (pin "1") (pinfunction "1_1") (pintype "passive"))
      (node (ref "C28") (pin "2") (pinfunction "2_2") (pintype "passive"))
      (node (ref "R37") (pin "1") (pinfunction "1_1") (pintype "passive"))
      (node (ref "R40") (pin "2") (pinfunction "2_2") (pintype "passive"))
      (node (ref "R41") (pin "1") (pinfunction "1_1") (pintype "passive"))
      (node (ref "X9") (pin "RING") (pinfunction "2_RING") (pintype "passive"))
    )
    (net (code "67") (name "Net-(X10-1)") (class "Default")
      (node (ref "C32") (pin "1") (pinfunction "1_1") (pintype "passive"))
      (node (ref "R43") (pin "1") (pinfunction "1_1") (pintype "passive"))
      (node (ref "R45") (pin "1") (pinfunction "1_1") (pintype "passive"))
      (node (ref "X10") (pin "SIGNAL") (pinfunction "1_SIGNAL") (pintype "passive"))
    )
    (net (code "68") (name "Net-(X10-2)") (class "Default")
      (node (ref "C30") (pin "1") (pinfunction "1_1") (pintype "passive"))
      (node (ref "C32") (pin "2") (pinfunction "2_2") (pintype "passive"))
      (node (ref "R42") (pin "1") (pinfunction "1_1") (pintype "passive"))
      (node (ref "R45") (pin "2") (pinfunction "2_2") (pintype "passive"))
      (node (ref "R46") (pin "1") (pinfunction "1_1") (pintype "passive"))
      (node (ref "X10") (pin "RING") (pinfunction "2_RING") (pintype "passive"))
    )
    (net (code "69") (name "Net-(X11-1)") (class "Default")
      (node (ref "C44") (pin "1") (pinfunction "1_1") (pintype "passive"))
      (node (ref "R53") (pin "1") (pinfunction "1_1") (pintype "passive"))
      (node (ref "R55") (pin "1") (pinfunction "1_1") (pintype "passive"))
      (node (ref "X11") (pin "SIGNAL") (pinfunction "1_SIGNAL") (pintype "passive"))
    )
    (net (code "70") (name "Net-(X11-2)") (class "Default")
      (node (ref "C42") (pin "1") (pinfunction "1_1") (pintype "passive"))
      (node (ref "C44") (pin "2") (pinfunction "2_2") (pintype "passive"))
      (node (ref "R52") (pin "1") (pinfunction "1_1") (pintype "passive"))
      (node (ref "R55") (pin "2") (pinfunction "2_2") (pintype "passive"))
      (node (ref "R56") (pin "1") (pinfunction "1_1") (pintype "passive"))
      (node (ref "X11") (pin "RING") (pinfunction "2_RING") (pintype "passive"))
    )
    (net (code "71") (name "Net-(X12-1)") (class "Default")
      (node (ref "C40") (pin "1") (pinfunction "1_1") (pintype "passive"))
      (node (ref "R48") (pin "1") (pinfunction "1_1") (pintype "passive"))
      (node (ref "R50") (pin "1") (pinfunction "1_1") (pintype "passive"))
      (node (ref "X12") (pin "SIGNAL") (pinfunction "1_SIGNAL") (pintype "passive"))
    )
    (net (code "72") (name "Net-(X12-2)") (class "Default")
      (node (ref "C38") (pin "1") (pinfunction "1_1") (pintype "passive"))
      (node (ref "C40") (pin "2") (pinfunction "2_2") (pintype "passive"))
      (node (ref "R47") (pin "1") (pinfunction "1_1") (pintype "passive"))
      (node (ref "R50") (pin "2") (pinfunction "2_2") (pintype "passive"))
      (node (ref "R51") (pin "1") (pinfunction "1_1") (pintype "passive"))
      (node (ref "X12") (pin "RING") (pinfunction "2_RING") (pintype "passive"))
    )
  )
)
